# RK3566_Power.net
KiCad netlist of a schematic drawn in Altium Designer
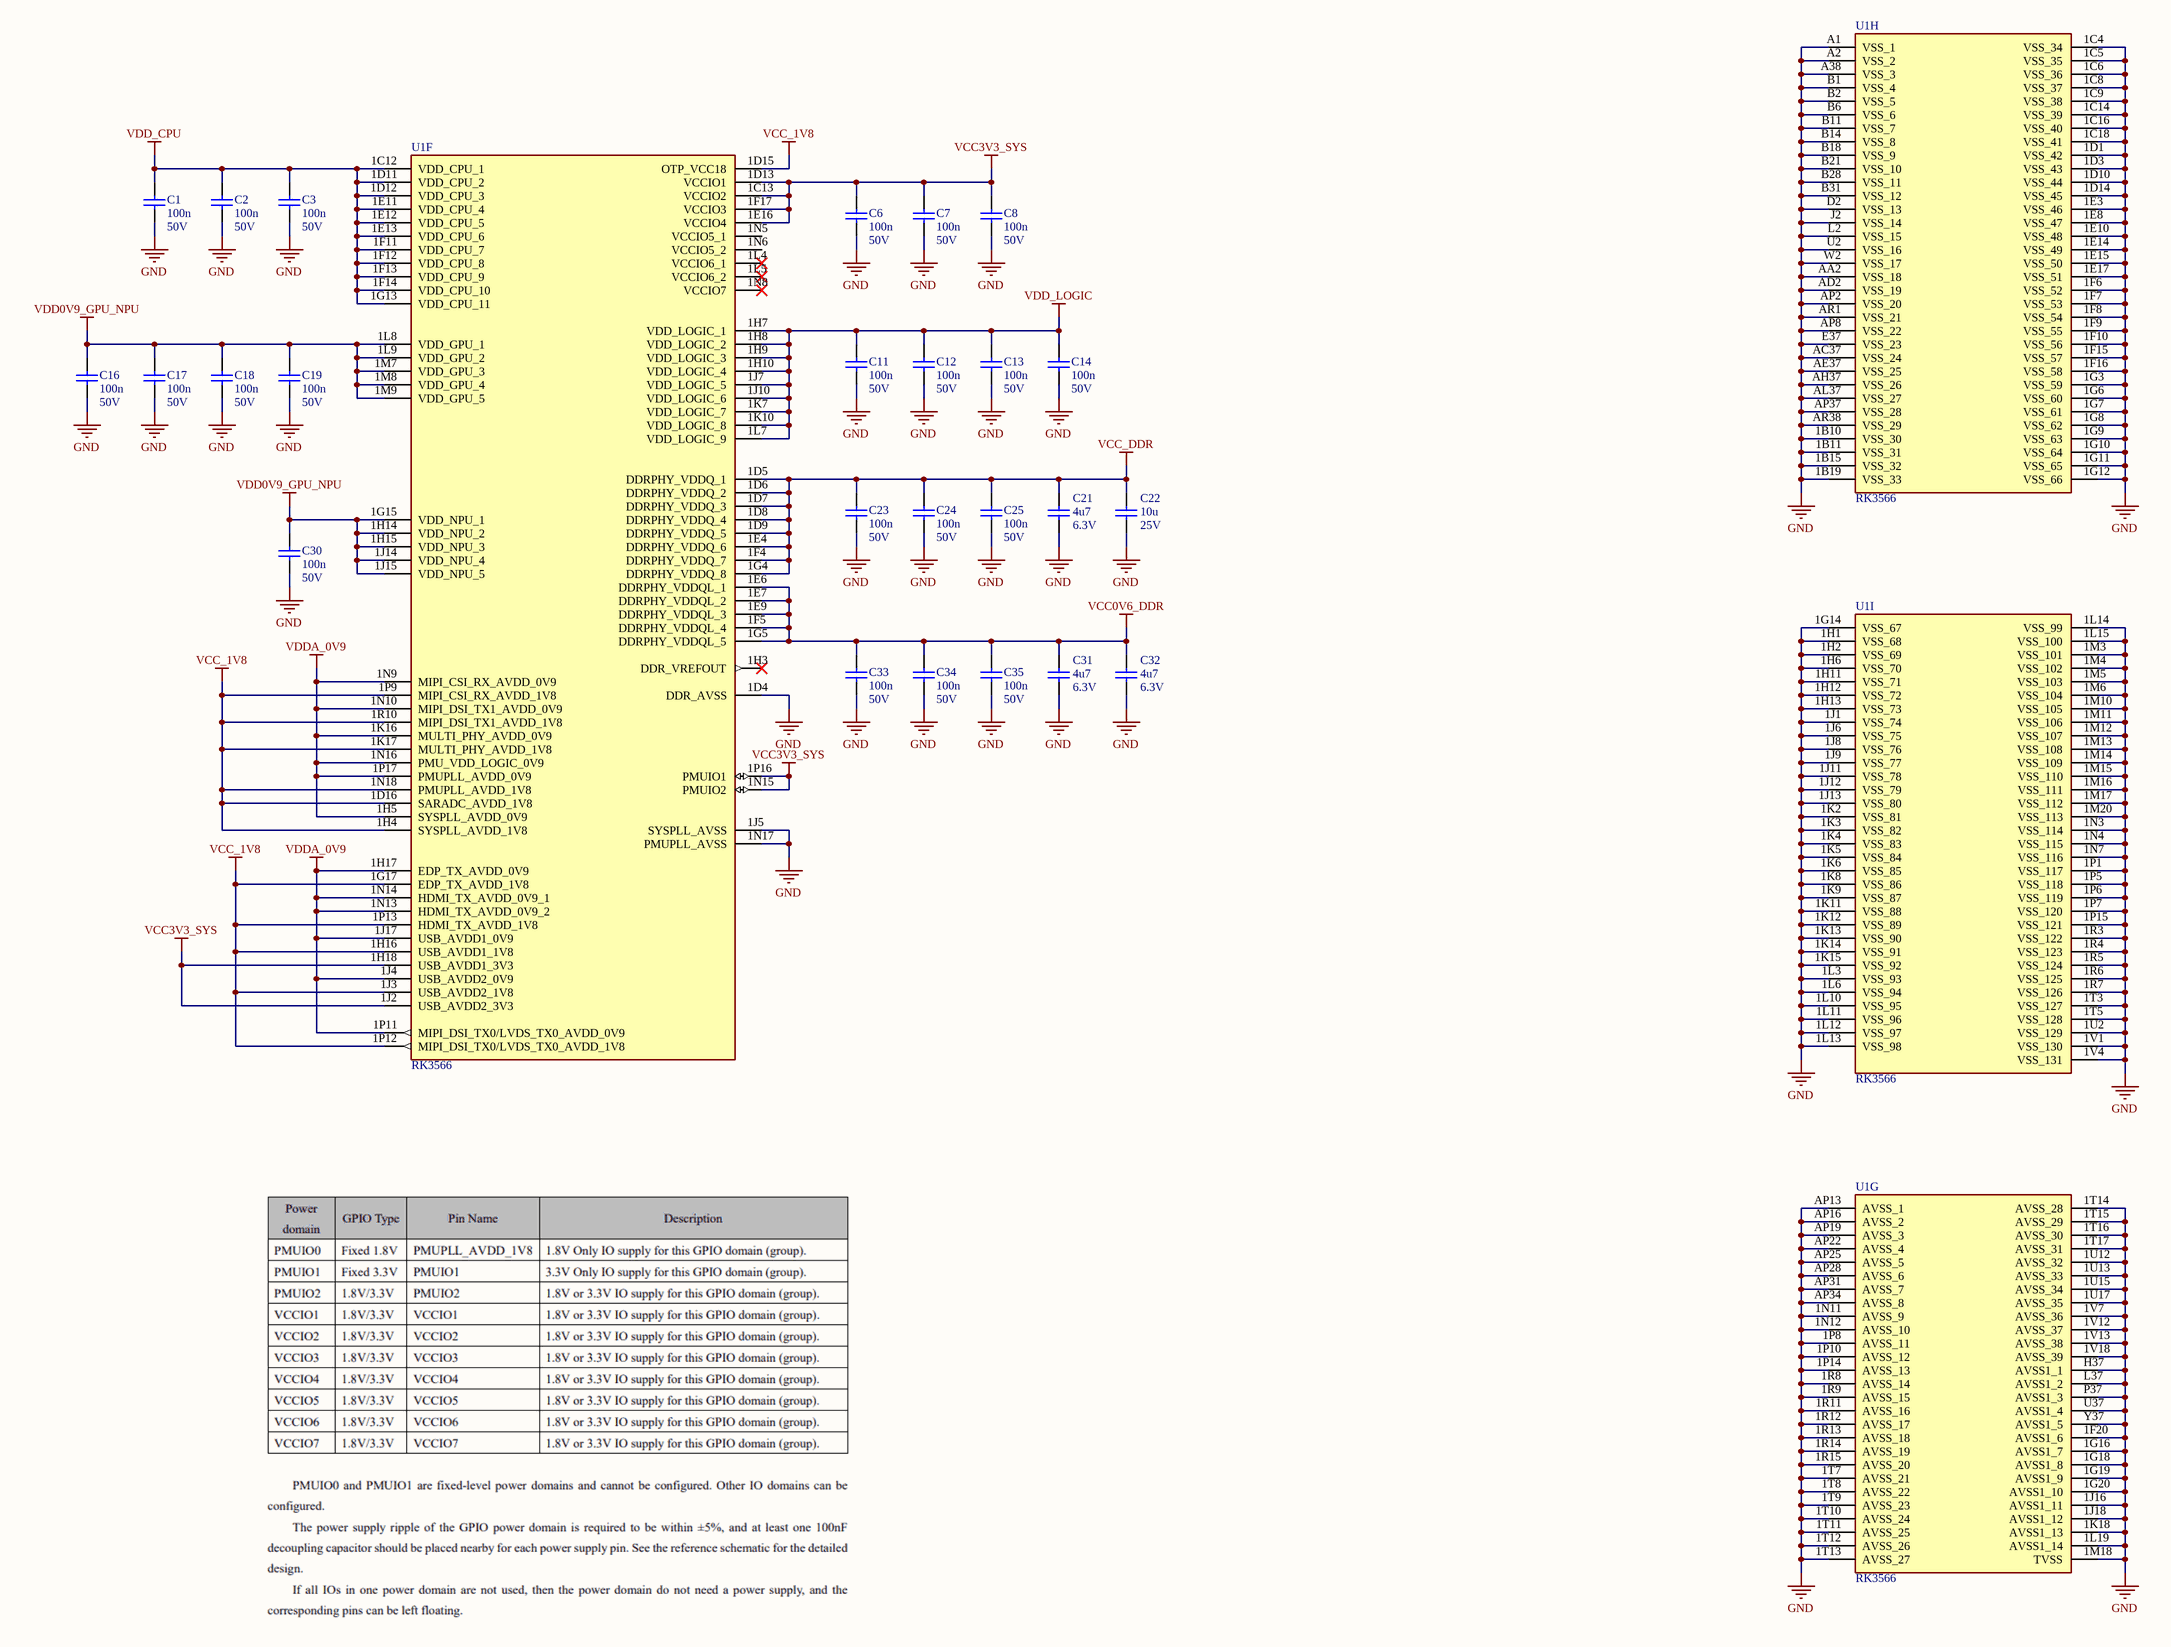
[diagram p0: RK3566_Power.SchDoc]

(export (version "E")
  (design (tool "Eeschema 10.0.6"))
  (components
    (comp (ref "C1")
      (value "100n")
      (footprint "GRM155R71H104KE14D")
      (description "CAP 100N 50V X7R 0402")
      (fields (field (name "VOLTAGE") "50V") (field (name "Comment") "GRM155R71H104KE14D"))
      (libsource (lib "PersonalAltiumLibrary") (part "GRM155R71H104KE14D"))
    )
    (comp (ref "C2")
      (value "100n")
      (footprint "GRM155R71H104KE14D")
      (description "CAP 100N 50V X7R 0402")
      (fields (field (name "VOLTAGE") "50V") (field (name "Comment") "GRM155R71H104KE14D"))
      (libsource (lib "PersonalAltiumLibrary") (part "GRM155R71H104KE14D"))
    )
    (comp (ref "C3")
      (value "100n")
      (footprint "GRM155R71H104KE14D")
      (description "CAP 100N 50V X7R 0402")
      (fields (field (name "VOLTAGE") "50V") (field (name "Comment") "GRM155R71H104KE14D"))
      (libsource (lib "PersonalAltiumLibrary") (part "GRM155R71H104KE14D"))
    )
    (comp (ref "C6")
      (value "100n")
      (footprint "GRM155R71H104KE14D")
      (description "CAP 100N 50V X7R 0402")
      (fields (field (name "VOLTAGE") "50V") (field (name "Comment") "GRM155R71H104KE14D"))
      (libsource (lib "PersonalAltiumLibrary") (part "GRM155R71H104KE14D"))
    )
    (comp (ref "C7")
      (value "100n")
      (footprint "GRM155R71H104KE14D")
      (description "CAP 100N 50V X7R 0402")
      (fields (field (name "VOLTAGE") "50V") (field (name "Comment") "GRM155R71H104KE14D"))
      (libsource (lib "PersonalAltiumLibrary") (part "GRM155R71H104KE14D"))
    )
    (comp (ref "C8")
      (value "100n")
      (footprint "GRM155R71H104KE14D")
      (description "CAP 100N 50V X7R 0402")
      (fields (field (name "VOLTAGE") "50V") (field (name "Comment") "GRM155R71H104KE14D"))
      (libsource (lib "PersonalAltiumLibrary") (part "GRM155R71H104KE14D"))
    )
    (comp (ref "C11")
      (value "100n")
      (footprint "GRM155R71H104KE14D")
      (description "CAP 100N 50V X7R 0402")
      (fields (field (name "VOLTAGE") "50V") (field (name "Comment") "GRM155R71H104KE14D"))
      (libsource (lib "PersonalAltiumLibrary") (part "GRM155R71H104KE14D"))
    )
    (comp (ref "C12")
      (value "100n")
      (footprint "GRM155R71H104KE14D")
      (description "CAP 100N 50V X7R 0402")
      (fields (field (name "VOLTAGE") "50V") (field (name "Comment") "GRM155R71H104KE14D"))
      (libsource (lib "PersonalAltiumLibrary") (part "GRM155R71H104KE14D"))
    )
    (comp (ref "C13")
      (value "100n")
      (footprint "GRM155R71H104KE14D")
      (description "CAP 100N 50V X7R 0402")
      (fields (field (name "VOLTAGE") "50V") (field (name "Comment") "GRM155R71H104KE14D"))
      (libsource (lib "PersonalAltiumLibrary") (part "GRM155R71H104KE14D"))
    )
    (comp (ref "C14")
      (value "100n")
      (footprint "GRM155R71H104KE14D")
      (description "CAP 100N 50V X7R 0402")
      (fields (field (name "VOLTAGE") "50V") (field (name "Comment") "GRM155R71H104KE14D"))
      (libsource (lib "PersonalAltiumLibrary") (part "GRM155R71H104KE14D"))
    )
    (comp (ref "C16")
      (value "100n")
      (footprint "GRM155R71H104KE14D")
      (description "CAP 100N 50V X7R 0402")
      (fields (field (name "VOLTAGE") "50V") (field (name "Comment") "GRM155R71H104KE14D"))
      (libsource (lib "PersonalAltiumLibrary") (part "GRM155R71H104KE14D"))
    )
    (comp (ref "C17")
      (value "100n")
      (footprint "GRM155R71H104KE14D")
      (description "CAP 100N 50V X7R 0402")
      (fields (field (name "VOLTAGE") "50V") (field (name "Comment") "GRM155R71H104KE14D"))
      (libsource (lib "PersonalAltiumLibrary") (part "GRM155R71H104KE14D"))
    )
    (comp (ref "C18")
      (value "100n")
      (footprint "GRM155R71H104KE14D")
      (description "CAP 100N 50V X7R 0402")
      (fields (field (name "VOLTAGE") "50V") (field (name "Comment") "GRM155R71H104KE14D"))
      (libsource (lib "PersonalAltiumLibrary") (part "GRM155R71H104KE14D"))
    )
    (comp (ref "C19")
      (value "100n")
      (footprint "GRM155R71H104KE14D")
      (description "CAP 100N 50V X7R 0402")
      (fields (field (name "VOLTAGE") "50V") (field (name "Comment") "GRM155R71H104KE14D"))
      (libsource (lib "PersonalAltiumLibrary") (part "GRM155R71H104KE14D"))
    )
    (comp (ref "C21")
      (value "4u7")
      (footprint "GRM155R60J475ME47D")
      (description "CAP 4.7U 6.3V X5R 0402")
      (fields (field (name "VOLTAGE") "6.3V") (field (name "Comment") "GRM155R60J475ME47D"))
      (libsource (lib "PersonalAltiumLibrary") (part "GRM155R60J475ME47D"))
    )
    (comp (ref "C22")
      (value "10u")
      (description "CAP 10U 25V X5R 0603")
      (fields (field (name "VOLTAGE") "25V") (field (name "Comment") "GRM188R61E106MA73D"))
      (libsource (lib "PersonalAltiumLibrary") (part "GRM188R61E106MA73D"))
    )
    (comp (ref "C23")
      (value "100n")
      (footprint "GRM155R71H104KE14D")
      (description "CAP 100N 50V X7R 0402")
      (fields (field (name "VOLTAGE") "50V") (field (name "Comment") "GRM155R71H104KE14D"))
      (libsource (lib "PersonalAltiumLibrary") (part "GRM155R71H104KE14D"))
    )
    (comp (ref "C24")
      (value "100n")
      (footprint "GRM155R71H104KE14D")
      (description "CAP 100N 50V X7R 0402")
      (fields (field (name "VOLTAGE") "50V") (field (name "Comment") "GRM155R71H104KE14D"))
      (libsource (lib "PersonalAltiumLibrary") (part "GRM155R71H104KE14D"))
    )
    (comp (ref "C25")
      (value "100n")
      (footprint "GRM155R71H104KE14D")
      (description "CAP 100N 50V X7R 0402")
      (fields (field (name "VOLTAGE") "50V") (field (name "Comment") "GRM155R71H104KE14D"))
      (libsource (lib "PersonalAltiumLibrary") (part "GRM155R71H104KE14D"))
    )
    (comp (ref "C30")
      (value "100n")
      (footprint "GRM155R71H104KE14D")
      (description "CAP 100N 50V X7R 0402")
      (fields (field (name "VOLTAGE") "50V") (field (name "Comment") "GRM155R71H104KE14D"))
      (libsource (lib "PersonalAltiumLibrary") (part "GRM155R71H104KE14D"))
    )
    (comp (ref "C31")
      (value "4u7")
      (footprint "GRM155R60J475ME47D")
      (description "CAP 4.7U 6.3V X5R 0402")
      (fields (field (name "VOLTAGE") "6.3V") (field (name "Comment") "GRM155R60J475ME47D"))
      (libsource (lib "PersonalAltiumLibrary") (part "GRM155R60J475ME47D"))
    )
    (comp (ref "C32")
      (value "4u7")
      (footprint "GRM155R60J475ME47D")
      (description "CAP 4.7U 6.3V X5R 0402")
      (fields (field (name "VOLTAGE") "6.3V") (field (name "Comment") "GRM155R60J475ME47D"))
      (libsource (lib "PersonalAltiumLibrary") (part "GRM155R60J475ME47D"))
    )
    (comp (ref "C33")
      (value "100n")
      (footprint "GRM155R71H104KE14D")
      (description "CAP 100N 50V X7R 0402")
      (fields (field (name "VOLTAGE") "50V") (field (name "Comment") "GRM155R71H104KE14D"))
      (libsource (lib "PersonalAltiumLibrary") (part "GRM155R71H104KE14D"))
    )
    (comp (ref "C34")
      (value "100n")
      (footprint "GRM155R71H104KE14D")
      (description "CAP 100N 50V X7R 0402")
      (fields (field (name "VOLTAGE") "50V") (field (name "Comment") "GRM155R71H104KE14D"))
      (libsource (lib "PersonalAltiumLibrary") (part "GRM155R71H104KE14D"))
    )
    (comp (ref "C35")
      (value "100n")
      (footprint "GRM155R71H104KE14D")
      (description "CAP 100N 50V X7R 0402")
      (fields (field (name "VOLTAGE") "50V") (field (name "Comment") "GRM155R71H104KE14D"))
      (libsource (lib "PersonalAltiumLibrary") (part "GRM155R71H104KE14D"))
    )
    (comp (ref "U1")
      (value "RK3566")
      (footprint "RK3566")
      (description "high-performance and low-power quad-core application processor")
      (fields (field (name "MF") "Fuzhou Rockchip Electronics Co"))
      (libsource (lib "PersonalAltiumLibrary") (part "RK3566"))
    )
  )
  (nets
    (net (code "1") (name "GND") (class "Default")
      (node (ref "C1") (pin "2") (pinfunction "2_2") (pintype "passive"))
      (node (ref "C11") (pin "2") (pinfunction "2_2") (pintype "passive"))
      (node (ref "C12") (pin "2") (pinfunction "2_2") (pintype "passive"))
      (node (ref "C13") (pin "2") (pinfunction "2_2") (pintype "passive"))
      (node (ref "C14") (pin "2") (pinfunction "2_2") (pintype "passive"))
      (node (ref "C16") (pin "2") (pinfunction "2_2") (pintype "passive"))
      (node (ref "C17") (pin "2") (pinfunction "2_2") (pintype "passive"))
      (node (ref "C18") (pin "2") (pinfunction "2_2") (pintype "passive"))
      (node (ref "C19") (pin "2") (pinfunction "2_2") (pintype "passive"))
      (node (ref "C2") (pin "2") (pinfunction "2_2") (pintype "passive"))
      (node (ref "C21") (pin "2") (pinfunction "2_2") (pintype "passive"))
      (node (ref "C22") (pin "2") (pinfunction "2_2") (pintype "passive"))
      (node (ref "C23") (pin "2") (pinfunction "2_2") (pintype "passive"))
      (node (ref "C24") (pin "2") (pinfunction "2_2") (pintype "passive"))
      (node (ref "C25") (pin "2") (pinfunction "2_2") (pintype "passive"))
      (node (ref "C3") (pin "2") (pinfunction "2_2") (pintype "passive"))
      (node (ref "C30") (pin "2") (pinfunction "2_2") (pintype "passive"))
      (node (ref "C31") (pin "2") (pinfunction "2_2") (pintype "passive"))
      (node (ref "C32") (pin "2") (pinfunction "2_2") (pintype "passive"))
      (node (ref "C33") (pin "2") (pinfunction "2_2") (pintype "passive"))
      (node (ref "C34") (pin "2") (pinfunction "2_2") (pintype "passive"))
      (node (ref "C35") (pin "2") (pinfunction "2_2") (pintype "passive"))
      (node (ref "C6") (pin "2") (pinfunction "2_2") (pintype "passive"))
      (node (ref "C7") (pin "2") (pinfunction "2_2") (pintype "passive"))
      (node (ref "C8") (pin "2") (pinfunction "2_2") (pintype "passive"))
      (node (ref "U1") (pin "1B10") (pinfunction "VSS_30_1B10") (pintype "power_in"))
      (node (ref "U1") (pin "1B11") (pinfunction "VSS_31_1B11") (pintype "power_in"))
      (node (ref "U1") (pin "1B15") (pinfunction "VSS_32_1B15") (pintype "power_in"))
      (node (ref "U1") (pin "1B19") (pinfunction "VSS_33_1B19") (pintype "power_in"))
      (node (ref "U1") (pin "1C14") (pinfunction "VSS_39_1C14") (pintype "power_in"))
      (node (ref "U1") (pin "1C16") (pinfunction "VSS_40_1C16") (pintype "power_in"))
      (node (ref "U1") (pin "1C18") (pinfunction "VSS_41_1C18") (pintype "power_in"))
      (node (ref "U1") (pin "1C4") (pinfunction "VSS_34_1C4") (pintype "power_in"))
      (node (ref "U1") (pin "1C5") (pinfunction "VSS_35_1C5") (pintype "power_in"))
      (node (ref "U1") (pin "1C6") (pinfunction "VSS_36_1C6") (pintype "power_in"))
      (node (ref "U1") (pin "1C8") (pinfunction "VSS_37_1C8") (pintype "power_in"))
      (node (ref "U1") (pin "1C9") (pinfunction "VSS_38_1C9") (pintype "power_in"))
      (node (ref "U1") (pin "1D1") (pinfunction "VSS_42_1D1") (pintype "power_in"))
      (node (ref "U1") (pin "1D10") (pinfunction "VSS_44_1D10") (pintype "power_in"))
      (node (ref "U1") (pin "1D14") (pinfunction "VSS_45_1D14") (pintype "power_in"))
      (node (ref "U1") (pin "1D3") (pinfunction "VSS_43_1D3") (pintype "power_in"))
      (node (ref "U1") (pin "1D4") (pinfunction "DDR_AVSS_1D4") (pintype "power_in"))
      (node (ref "U1") (pin "1E10") (pinfunction "VSS_48_1E10") (pintype "power_in"))
      (node (ref "U1") (pin "1E14") (pinfunction "VSS_49_1E14") (pintype "power_in"))
      (node (ref "U1") (pin "1E15") (pinfunction "VSS_50_1E15") (pintype "power_in"))
      (node (ref "U1") (pin "1E17") (pinfunction "VSS_51_1E17") (pintype "power_in"))
      (node (ref "U1") (pin "1E3") (pinfunction "VSS_46_1E3") (pintype "power_in"))
      (node (ref "U1") (pin "1E8") (pinfunction "VSS_47_1E8") (pintype "power_in"))
      (node (ref "U1") (pin "1F10") (pinfunction "VSS_56_1F10") (pintype "power_in"))
      (node (ref "U1") (pin "1F15") (pinfunction "VSS_57_1F15") (pintype "power_in"))
      (node (ref "U1") (pin "1F16") (pinfunction "VSS_58_1F16") (pintype "power_in"))
      (node (ref "U1") (pin "1F20") (pinfunction "AVSS1_6_1F20") (pintype "power_in"))
      (node (ref "U1") (pin "1F6") (pinfunction "VSS_52_1F6") (pintype "power_in"))
      (node (ref "U1") (pin "1F7") (pinfunction "VSS_53_1F7") (pintype "power_in"))
      (node (ref "U1") (pin "1F8") (pinfunction "VSS_54_1F8") (pintype "power_in"))
      (node (ref "U1") (pin "1F9") (pinfunction "VSS_55_1F9") (pintype "power_in"))
      (node (ref "U1") (pin "1G10") (pinfunction "VSS_64_1G10") (pintype "power_in"))
      (node (ref "U1") (pin "1G11") (pinfunction "VSS_65_1G11") (pintype "power_in"))
      (node (ref "U1") (pin "1G12") (pinfunction "VSS_66_1G12") (pintype "power_in"))
      (node (ref "U1") (pin "1G14") (pinfunction "VSS_67_1G14") (pintype "power_in"))
      (node (ref "U1") (pin "1G16") (pinfunction "AVSS1_7_1G16") (pintype "power_in"))
      (node (ref "U1") (pin "1G18") (pinfunction "AVSS1_8_1G18") (pintype "power_in"))
      (node (ref "U1") (pin "1G19") (pinfunction "AVSS1_9_1G19") (pintype "power_in"))
      (node (ref "U1") (pin "1G20") (pinfunction "AVSS1_10_1G20") (pintype "power_in"))
      (node (ref "U1") (pin "1G3") (pinfunction "VSS_59_1G3") (pintype "power_in"))
      (node (ref "U1") (pin "1G6") (pinfunction "VSS_60_1G6") (pintype "power_in"))
      (node (ref "U1") (pin "1G7") (pinfunction "VSS_61_1G7") (pintype "power_in"))
      (node (ref "U1") (pin "1G8") (pinfunction "VSS_62_1G8") (pintype "power_in"))
      (node (ref "U1") (pin "1G9") (pinfunction "VSS_63_1G9") (pintype "power_in"))
      (node (ref "U1") (pin "1H1") (pinfunction "VSS_68_1H1") (pintype "power_in"))
      (node (ref "U1") (pin "1H11") (pinfunction "VSS_71_1H11") (pintype "power_in"))
      (node (ref "U1") (pin "1H12") (pinfunction "VSS_72_1H12") (pintype "power_in"))
      (node (ref "U1") (pin "1H13") (pinfunction "VSS_73_1H13") (pintype "power_in"))
      (node (ref "U1") (pin "1H2") (pinfunction "VSS_69_1H2") (pintype "power_in"))
      (node (ref "U1") (pin "1H6") (pinfunction "VSS_70_1H6") (pintype "power_in"))
      (node (ref "U1") (pin "1J1") (pinfunction "VSS_74_1J1") (pintype "power_in"))
      (node (ref "U1") (pin "1J11") (pinfunction "VSS_78_1J11") (pintype "power_in"))
      (node (ref "U1") (pin "1J12") (pinfunction "VSS_79_1J12") (pintype "power_in"))
      (node (ref "U1") (pin "1J13") (pinfunction "VSS_80_1J13") (pintype "power_in"))
      (node (ref "U1") (pin "1J16") (pinfunction "AVSS1_11_1J16") (pintype "power_in"))
      (node (ref "U1") (pin "1J18") (pinfunction "AVSS1_12_1J18") (pintype "power_in"))
      (node (ref "U1") (pin "1J5") (pinfunction "SYSPLL_AVSS_1J5") (pintype "power_in"))
      (node (ref "U1") (pin "1J6") (pinfunction "VSS_75_1J6") (pintype "power_in"))
      (node (ref "U1") (pin "1J8") (pinfunction "VSS_76_1J8") (pintype "power_in"))
      (node (ref "U1") (pin "1J9") (pinfunction "VSS_77_1J9") (pintype "power_in"))
      (node (ref "U1") (pin "1K11") (pinfunction "VSS_88_1K11") (pintype "power_in"))
      (node (ref "U1") (pin "1K12") (pinfunction "VSS_89_1K12") (pintype "power_in"))
      (node (ref "U1") (pin "1K13") (pinfunction "VSS_90_1K13") (pintype "power_in"))
      (node (ref "U1") (pin "1K14") (pinfunction "VSS_91_1K14") (pintype "power_in"))
      (node (ref "U1") (pin "1K15") (pinfunction "VSS_92_1K15") (pintype "power_in"))
      (node (ref "U1") (pin "1K18") (pinfunction "AVSS1_13_1K18") (pintype "power_in"))
      (node (ref "U1") (pin "1K2") (pinfunction "VSS_81_1K2") (pintype "power_in"))
      (node (ref "U1") (pin "1K3") (pinfunction "VSS_82_1K3") (pintype "power_in"))
      (node (ref "U1") (pin "1K4") (pinfunction "VSS_83_1K4") (pintype "power_in"))
      (node (ref "U1") (pin "1K5") (pinfunction "VSS_84_1K5") (pintype "power_in"))
      (node (ref "U1") (pin "1K6") (pinfunction "VSS_85_1K6") (pintype "power_in"))
      (node (ref "U1") (pin "1K8") (pinfunction "VSS_86_1K8") (pintype "power_in"))
      (node (ref "U1") (pin "1K9") (pinfunction "VSS_87_1K9") (pintype "power_in"))
      (node (ref "U1") (pin "1L10") (pinfunction "VSS_95_1L10") (pintype "power_in"))
      (node (ref "U1") (pin "1L11") (pinfunction "VSS_96_1L11") (pintype "power_in"))
      (node (ref "U1") (pin "1L12") (pinfunction "VSS_97_1L12") (pintype "power_in"))
      (node (ref "U1") (pin "1L13") (pinfunction "VSS_98_1L13") (pintype "power_in"))
      (node (ref "U1") (pin "1L14") (pinfunction "VSS_99_1L14") (pintype "power_in"))
      (node (ref "U1") (pin "1L15") (pinfunction "VSS_100_1L15") (pintype "power_in"))
      (node (ref "U1") (pin "1L19") (pinfunction "AVSS1_14_1L19") (pintype "power_in"))
      (node (ref "U1") (pin "1L3") (pinfunction "VSS_93_1L3") (pintype "power_in"))
      (node (ref "U1") (pin "1L6") (pinfunction "VSS_94_1L6") (pintype "power_in"))
      (node (ref "U1") (pin "1M10") (pinfunction "VSS_105_1M10") (pintype "power_in"))
      (node (ref "U1") (pin "1M11") (pinfunction "VSS_106_1M11") (pintype "power_in"))
      (node (ref "U1") (pin "1M12") (pinfunction "VSS_107_1M12") (pintype "power_in"))
      (node (ref "U1") (pin "1M13") (pinfunction "VSS_108_1M13") (pintype "power_in"))
      (node (ref "U1") (pin "1M14") (pinfunction "VSS_109_1M14") (pintype "power_in"))
      (node (ref "U1") (pin "1M15") (pinfunction "VSS_110_1M15") (pintype "power_in"))
      (node (ref "U1") (pin "1M16") (pinfunction "VSS_111_1M16") (pintype "power_in"))
      (node (ref "U1") (pin "1M17") (pinfunction "VSS_112_1M17") (pintype "power_in"))
      (node (ref "U1") (pin "1M18") (pinfunction "TVSS_1M18") (pintype "power_in"))
      (node (ref "U1") (pin "1M20") (pinfunction "VSS_113_1M20") (pintype "power_in"))
      (node (ref "U1") (pin "1M3") (pinfunction "VSS_101_1M3") (pintype "power_in"))
      (node (ref "U1") (pin "1M4") (pinfunction "VSS_102_1M4") (pintype "power_in"))
      (node (ref "U1") (pin "1M5") (pinfunction "VSS_103_1M5") (pintype "power_in"))
      (node (ref "U1") (pin "1M6") (pinfunction "VSS_104_1M6") (pintype "power_in"))
      (node (ref "U1") (pin "1N11") (pinfunction "AVSS_9_1N11") (pintype "power_in"))
      (node (ref "U1") (pin "1N12") (pinfunction "AVSS_10_1N12") (pintype "power_in"))
      (node (ref "U1") (pin "1N17") (pinfunction "PMUPLL_AVSS_1N17") (pintype "power_in"))
      (node (ref "U1") (pin "1N3") (pinfunction "VSS_114_1N3") (pintype "power_in"))
      (node (ref "U1") (pin "1N4") (pinfunction "VSS_115_1N4") (pintype "power_in"))
      (node (ref "U1") (pin "1N7") (pinfunction "VSS_116_1N7") (pintype "power_in"))
      (node (ref "U1") (pin "1P1") (pinfunction "VSS_117_1P1") (pintype "power_in"))
      (node (ref "U1") (pin "1P10") (pinfunction "AVSS_12_1P10") (pintype "power_in"))
      (node (ref "U1") (pin "1P14") (pinfunction "AVSS_13_1P14") (pintype "power_in"))
      (node (ref "U1") (pin "1P15") (pinfunction "VSS_121_1P15") (pintype "power_in"))
      (node (ref "U1") (pin "1P5") (pinfunction "VSS_118_1P5") (pintype "power_in"))
      (node (ref "U1") (pin "1P6") (pinfunction "VSS_119_1P6") (pintype "power_in"))
      (node (ref "U1") (pin "1P7") (pinfunction "VSS_120_1P7") (pintype "power_in"))
      (node (ref "U1") (pin "1P8") (pinfunction "AVSS_11_1P8") (pintype "power_in"))
      (node (ref "U1") (pin "1R11") (pinfunction "AVSS_16_1R11") (pintype "power_in"))
      (node (ref "U1") (pin "1R12") (pinfunction "AVSS_17_1R12") (pintype "power_in"))
      (node (ref "U1") (pin "1R13") (pinfunction "AVSS_18_1R13") (pintype "power_in"))
      (node (ref "U1") (pin "1R14") (pinfunction "AVSS_19_1R14") (pintype "power_in"))
      (node (ref "U1") (pin "1R15") (pinfunction "AVSS_20_1R15") (pintype "power_in"))
      (node (ref "U1") (pin "1R3") (pinfunction "VSS_122_1R3") (pintype "power_in"))
      (node (ref "U1") (pin "1R4") (pinfunction "VSS_123_1R4") (pintype "power_in"))
      (node (ref "U1") (pin "1R5") (pinfunction "VSS_124_1R5") (pintype "power_in"))
      (node (ref "U1") (pin "1R6") (pinfunction "VSS_125_1R6") (pintype "power_in"))
      (node (ref "U1") (pin "1R7") (pinfunction "VSS_126_1R7") (pintype "power_in"))
      (node (ref "U1") (pin "1R8") (pinfunction "AVSS_14_1R8") (pintype "power_in"))
      (node (ref "U1") (pin "1R9") (pinfunction "AVSS_15_1R9") (pintype "power_in"))
      (node (ref "U1") (pin "1T10") (pinfunction "AVSS_24_1T10") (pintype "power_in"))
      (node (ref "U1") (pin "1T11") (pinfunction "AVSS_25_1T11") (pintype "power_in"))
      (node (ref "U1") (pin "1T12") (pinfunction "AVSS_26_1T12") (pintype "power_in"))
      (node (ref "U1") (pin "1T13") (pinfunction "AVSS_27_1T13") (pintype "power_in"))
      (node (ref "U1") (pin "1T14") (pinfunction "AVSS_28_1T14") (pintype "power_in"))
      (node (ref "U1") (pin "1T15") (pinfunction "AVSS_29_1T15") (pintype "power_in"))
      (node (ref "U1") (pin "1T16") (pinfunction "AVSS_30_1T16") (pintype "power_in"))
      (node (ref "U1") (pin "1T17") (pinfunction "AVSS_31_1T17") (pintype "power_in"))
      (node (ref "U1") (pin "1T3") (pinfunction "VSS_127_1T3") (pintype "power_in"))
      (node (ref "U1") (pin "1T5") (pinfunction "VSS_128_1T5") (pintype "power_in"))
      (node (ref "U1") (pin "1T7") (pinfunction "AVSS_21_1T7") (pintype "power_in"))
      (node (ref "U1") (pin "1T8") (pinfunction "AVSS_22_1T8") (pintype "power_in"))
      (node (ref "U1") (pin "1T9") (pinfunction "AVSS_23_1T9") (pintype "power_in"))
      (node (ref "U1") (pin "1U12") (pinfunction "AVSS_32_1U12") (pintype "power_in"))
      (node (ref "U1") (pin "1U13") (pinfunction "AVSS_33_1U13") (pintype "power_in"))
      (node (ref "U1") (pin "1U15") (pinfunction "AVSS_34_1U15") (pintype "power_in"))
      (node (ref "U1") (pin "1U17") (pinfunction "AVSS_35_1U17") (pintype "power_in"))
      (node (ref "U1") (pin "1U2") (pinfunction "VSS_129_1U2") (pintype "power_in"))
      (node (ref "U1") (pin "1V1") (pinfunction "VSS_130_1V1") (pintype "power_in"))
      (node (ref "U1") (pin "1V12") (pinfunction "AVSS_37_1V12") (pintype "power_in"))
      (node (ref "U1") (pin "1V13") (pinfunction "AVSS_38_1V13") (pintype "power_in"))
      (node (ref "U1") (pin "1V18") (pinfunction "AVSS_39_1V18") (pintype "power_in"))
      (node (ref "U1") (pin "1V4") (pinfunction "VSS_131_1V4") (pintype "power_in"))
      (node (ref "U1") (pin "1V7") (pinfunction "AVSS_36_1V7") (pintype "power_in"))
      (node (ref "U1") (pin "A1") (pinfunction "VSS_1_A1") (pintype "power_in"))
      (node (ref "U1") (pin "A2") (pinfunction "VSS_2_A2") (pintype "power_in"))
      (node (ref "U1") (pin "A38") (pinfunction "VSS_3_A38") (pintype "power_in"))
      (node (ref "U1") (pin "AA2") (pinfunction "VSS_18_AA2") (pintype "power_in"))
      (node (ref "U1") (pin "AC37") (pinfunction "VSS_24_AC37") (pintype "power_in"))
      (node (ref "U1") (pin "AD2") (pinfunction "VSS_19_AD2") (pintype "power_in"))
      (node (ref "U1") (pin "AE37") (pinfunction "VSS_25_AE37") (pintype "power_in"))
      (node (ref "U1") (pin "AH37") (pinfunction "VSS_26_AH37") (pintype "power_in"))
      (node (ref "U1") (pin "AL37") (pinfunction "VSS_27_AL37") (pintype "power_in"))
      (node (ref "U1") (pin "AP13") (pinfunction "AVSS_1_AP13") (pintype "power_in"))
      (node (ref "U1") (pin "AP16") (pinfunction "AVSS_2_AP16") (pintype "power_in"))
      (node (ref "U1") (pin "AP19") (pinfunction "AVSS_3_AP19") (pintype "power_in"))
      (node (ref "U1") (pin "AP2") (pinfunction "VSS_20_AP2") (pintype "power_in"))
      (node (ref "U1") (pin "AP22") (pinfunction "AVSS_4_AP22") (pintype "power_in"))
      (node (ref "U1") (pin "AP25") (pinfunction "AVSS_5_AP25") (pintype "power_in"))
      (node (ref "U1") (pin "AP28") (pinfunction "AVSS_6_AP28") (pintype "power_in"))
      (node (ref "U1") (pin "AP31") (pinfunction "AVSS_7_AP31") (pintype "power_in"))
      (node (ref "U1") (pin "AP34") (pinfunction "AVSS_8_AP34") (pintype "power_in"))
      (node (ref "U1") (pin "AP37") (pinfunction "VSS_28_AP37") (pintype "power_in"))
      (node (ref "U1") (pin "AP8") (pinfunction "VSS_22_AP8") (pintype "power_in"))
      (node (ref "U1") (pin "AR1") (pinfunction "VSS_21_AR1") (pintype "power_in"))
      (node (ref "U1") (pin "AR38") (pinfunction "VSS_29_AR38") (pintype "power_in"))
      (node (ref "U1") (pin "B1") (pinfunction "VSS_4_B1") (pintype "power_in"))
      (node (ref "U1") (pin "B11") (pinfunction "VSS_7_B11") (pintype "power_in"))
      (node (ref "U1") (pin "B14") (pinfunction "VSS_8_B14") (pintype "power_in"))
      (node (ref "U1") (pin "B18") (pinfunction "VSS_9_B18") (pintype "power_in"))
      (node (ref "U1") (pin "B2") (pinfunction "VSS_5_B2") (pintype "power_in"))
      (node (ref "U1") (pin "B21") (pinfunction "VSS_10_B21") (pintype "power_in"))
      (node (ref "U1") (pin "B28") (pinfunction "VSS_11_B28") (pintype "power_in"))
      (node (ref "U1") (pin "B31") (pinfunction "VSS_12_B31") (pintype "power_in"))
      (node (ref "U1") (pin "B6") (pinfunction "VSS_6_B6") (pintype "power_in"))
      (node (ref "U1") (pin "D2") (pinfunction "VSS_13_D2") (pintype "power_in"))
      (node (ref "U1") (pin "E37") (pinfunction "VSS_23_E37") (pintype "power_in"))
      (node (ref "U1") (pin "H37") (pinfunction "AVSS1_1_H37") (pintype "power_in"))
      (node (ref "U1") (pin "J2") (pinfunction "VSS_14_J2") (pintype "power_in"))
      (node (ref "U1") (pin "L2") (pinfunction "VSS_15_L2") (pintype "power_in"))
      (node (ref "U1") (pin "L37") (pinfunction "AVSS1_2_L37") (pintype "power_in"))
      (node (ref "U1") (pin "P37") (pinfunction "AVSS1_3_P37") (pintype "power_in"))
      (node (ref "U1") (pin "U2") (pinfunction "VSS_16_U2") (pintype "power_in"))
      (node (ref "U1") (pin "U37") (pinfunction "AVSS1_4_U37") (pintype "power_in"))
      (node (ref "U1") (pin "W2") (pinfunction "VSS_17_W2") (pintype "power_in"))
      (node (ref "U1") (pin "Y37") (pinfunction "AVSS1_5_Y37") (pintype "power_in"))
    )
    (net (code "2") (name "VCC0V6_DDR") (class "Default")
      (node (ref "C31") (pin "1") (pinfunction "1_1") (pintype "passive"))
      (node (ref "C32") (pin "1") (pinfunction "1_1") (pintype "passive"))
      (node (ref "C33") (pin "1") (pinfunction "1_1") (pintype "passive"))
      (node (ref "C34") (pin "1") (pinfunction "1_1") (pintype "passive"))
      (node (ref "C35") (pin "1") (pinfunction "1_1") (pintype "passive"))
      (node (ref "U1") (pin "1E6") (pinfunction "DDRPHY_VDDQL_1_1E6") (pintype "power_in"))
      (node (ref "U1") (pin "1E7") (pinfunction "DDRPHY_VDDQL_2_1E7") (pintype "power_in"))
      (node (ref "U1") (pin "1E9") (pinfunction "DDRPHY_VDDQL_3_1E9") (pintype "power_in"))
      (node (ref "U1") (pin "1F5") (pinfunction "DDRPHY_VDDQL_4_1F5") (pintype "power_in"))
      (node (ref "U1") (pin "1G5") (pinfunction "DDRPHY_VDDQL_5_1G5") (pintype "power_in"))
    )
    (net (code "3") (name "VCC3V3_SYS") (class "Default")
      (node (ref "C6") (pin "1") (pinfunction "1_1") (pintype "passive"))
      (node (ref "C7") (pin "1") (pinfunction "1_1") (pintype "passive"))
      (node (ref "C8") (pin "1") (pinfunction "1_1") (pintype "passive"))
      (node (ref "U1") (pin "1C13") (pinfunction "VCCIO2_1C13") (pintype "power_in"))
      (node (ref "U1") (pin "1D13") (pinfunction "VCCIO1_1D13") (pintype "power_in"))
      (node (ref "U1") (pin "1E16") (pinfunction "VCCIO4_1E16") (pintype "power_in"))
      (node (ref "U1") (pin "1F17") (pinfunction "VCCIO3_1F17") (pintype "power_in"))
      (node (ref "U1") (pin "1H18") (pinfunction "USB_AVDD1_3V3_1H18") (pintype "power_in"))
      (node (ref "U1") (pin "1J2") (pinfunction "USB_AVDD2_3V3_1J2") (pintype "power_in"))
      (node (ref "U1") (pin "1N15") (pinfunction "PMUIO2_1N15") (pintype "bidirectional"))
      (node (ref "U1") (pin "1P16") (pinfunction "PMUIO1_1P16") (pintype "bidirectional"))
    )
    (net (code "4") (name "VCC_1V8") (class "Default")
      (node (ref "U1") (pin "1D15") (pinfunction "OTP_VCC18_1D15") (pintype "power_in"))
      (node (ref "U1") (pin "1D16") (pinfunction "SARADC_AVDD_1V8_1D16") (pintype "power_in"))
      (node (ref "U1") (pin "1G17") (pinfunction "EDP_TX_AVDD_1V8_1G17") (pintype "power_in"))
      (node (ref "U1") (pin "1H16") (pinfunction "USB_AVDD1_1V8_1H16") (pintype "power_in"))
      (node (ref "U1") (pin "1H4") (pinfunction "SYSPLL_AVDD_1V8_1H4") (pintype "power_in"))
      (node (ref "U1") (pin "1J3") (pinfunction "USB_AVDD2_1V8_1J3") (pintype "power_in"))
      (node (ref "U1") (pin "1K17") (pinfunction "MULTI_PHY_AVDD_1V8_1K17") (pintype "power_in"))
      (node (ref "U1") (pin "1N18") (pinfunction "PMUPLL_AVDD_1V8_1N18") (pintype "power_in"))
      (node (ref "U1") (pin "1P12") (pinfunction "MIPI_DSI_TX0/LVDS_TX0_AVDD_1V8_1P12") (pintype "output"))
      (node (ref "U1") (pin "1P13") (pinfunction "HDMI_TX_AVDD_1V8_1P13") (pintype "power_in"))
      (node (ref "U1") (pin "1P9") (pinfunction "MIPI_CSI_RX_AVDD_1V8_1P9") (pintype "power_in"))
      (node (ref "U1") (pin "1R10") (pinfunction "MIPI_DSI_TX1_AVDD_1V8_1R10") (pintype "power_in"))
    )
    (net (code "5") (name "VCC_DDR") (class "Default")
      (node (ref "C21") (pin "1") (pinfunction "1_1") (pintype "passive"))
      (node (ref "C22") (pin "1") (pinfunction "1_1") (pintype "passive"))
      (node (ref "C23") (pin "1") (pinfunction "1_1") (pintype "passive"))
      (node (ref "C24") (pin "1") (pinfunction "1_1") (pintype "passive"))
      (node (ref "C25") (pin "1") (pinfunction "1_1") (pintype "passive"))
      (node (ref "U1") (pin "1D5") (pinfunction "DDRPHY_VDDQ_1_1D5") (pintype "power_in"))
      (node (ref "U1") (pin "1D6") (pinfunction "DDRPHY_VDDQ_2_1D6") (pintype "power_in"))
      (node (ref "U1") (pin "1D7") (pinfunction "DDRPHY_VDDQ_3_1D7") (pintype "power_in"))
      (node (ref "U1") (pin "1D8") (pinfunction "DDRPHY_VDDQ_4_1D8") (pintype "power_in"))
      (node (ref "U1") (pin "1D9") (pinfunction "DDRPHY_VDDQ_5_1D9") (pintype "power_in"))
      (node (ref "U1") (pin "1E4") (pinfunction "DDRPHY_VDDQ_6_1E4") (pintype "power_in"))
      (node (ref "U1") (pin "1F4") (pinfunction "DDRPHY_VDDQ_7_1F4") (pintype "power_in"))
      (node (ref "U1") (pin "1G4") (pinfunction "DDRPHY_VDDQ_8_1G4") (pintype "power_in"))
    )
    (net (code "6") (name "VDD0V9_GPU_NPU") (class "Default")
      (node (ref "C16") (pin "1") (pinfunction "1_1") (pintype "passive"))
      (node (ref "C17") (pin "1") (pinfunction "1_1") (pintype "passive"))
      (node (ref "C18") (pin "1") (pinfunction "1_1") (pintype "passive"))
      (node (ref "C19") (pin "1") (pinfunction "1_1") (pintype "passive"))
      (node (ref "C30") (pin "1") (pinfunction "1_1") (pintype "passive"))
      (node (ref "U1") (pin "1G15") (pinfunction "VDD_NPU_1_1G15") (pintype "power_in"))
      (node (ref "U1") (pin "1H14") (pinfunction "VDD_NPU_2_1H14") (pintype "power_in"))
      (node (ref "U1") (pin "1H15") (pinfunction "VDD_NPU_3_1H15") (pintype "power_in"))
      (node (ref "U1") (pin "1J14") (pinfunction "VDD_NPU_4_1J14") (pintype "power_in"))
      (node (ref "U1") (pin "1J15") (pinfunction "VDD_NPU_5_1J15") (pintype "power_in"))
      (node (ref "U1") (pin "1L8") (pinfunction "VDD_GPU_1_1L8") (pintype "power_in"))
      (node (ref "U1") (pin "1L9") (pinfunction "VDD_GPU_2_1L9") (pintype "power_in"))
      (node (ref "U1") (pin "1M7") (pinfunction "VDD_GPU_3_1M7") (pintype "power_in"))
      (node (ref "U1") (pin "1M8") (pinfunction "VDD_GPU_4_1M8") (pintype "power_in"))
      (node (ref "U1") (pin "1M9") (pinfunction "VDD_GPU_5_1M9") (pintype "power_in"))
    )
    (net (code "7") (name "VDDA_0V9") (class "Default")
      (node (ref "U1") (pin "1H17") (pinfunction "EDP_TX_AVDD_0V9_1H17") (pintype "power_in"))
      (node (ref "U1") (pin "1H5") (pinfunction "SYSPLL_AVDD_0V9_1H5") (pintype "power_in"))
      (node (ref "U1") (pin "1J17") (pinfunction "USB_AVDD1_0V9_1J17") (pintype "power_in"))
      (node (ref "U1") (pin "1J4") (pinfunction "USB_AVDD2_0V9_1J4") (pintype "power_in"))
      (node (ref "U1") (pin "1K16") (pinfunction "MULTI_PHY_AVDD_0V9_1K16") (pintype "power_in"))
      (node (ref "U1") (pin "1N10") (pinfunction "MIPI_DSI_TX1_AVDD_0V9_1N10") (pintype "power_in"))
      (node (ref "U1") (pin "1N13") (pinfunction "HDMI_TX_AVDD_0V9_2_1N13") (pintype "power_in"))
      (node (ref "U1") (pin "1N14") (pinfunction "HDMI_TX_AVDD_0V9_1_1N14") (pintype "power_in"))
      (node (ref "U1") (pin "1N16") (pinfunction "PMU_VDD_LOGIC_0V9_1N16") (pintype "power_in"))
      (node (ref "U1") (pin "1N9") (pinfunction "MIPI_CSI_RX_AVDD_0V9_1N9") (pintype "power_in"))
      (node (ref "U1") (pin "1P11") (pinfunction "MIPI_DSI_TX0/LVDS_TX0_AVDD_0V9_1P11") (pintype "output"))
      (node (ref "U1") (pin "1P17") (pinfunction "PMUPLL_AVDD_0V9_1P17") (pintype "power_in"))
    )
    (net (code "8") (name "VDD_CPU") (class "Default")
      (node (ref "C1") (pin "1") (pinfunction "1_1") (pintype "passive"))
      (node (ref "C2") (pin "1") (pinfunction "1_1") (pintype "passive"))
      (node (ref "C3") (pin "1") (pinfunction "1_1") (pintype "passive"))
      (node (ref "U1") (pin "1C12") (pinfunction "VDD_CPU_1_1C12") (pintype "power_in"))
      (node (ref "U1") (pin "1D11") (pinfunction "VDD_CPU_2_1D11") (pintype "power_in"))
      (node (ref "U1") (pin "1D12") (pinfunction "VDD_CPU_3_1D12") (pintype "power_in"))
      (node (ref "U1") (pin "1E11") (pinfunction "VDD_CPU_4_1E11") (pintype "power_in"))
      (node (ref "U1") (pin "1E12") (pinfunction "VDD_CPU_5_1E12") (pintype "power_in"))
      (node (ref "U1") (pin "1E13") (pinfunction "VDD_CPU_6_1E13") (pintype "power_in"))
      (node (ref "U1") (pin "1F11") (pinfunction "VDD_CPU_7_1F11") (pintype "power_in"))
      (node (ref "U1") (pin "1F12") (pinfunction "VDD_CPU_8_1F12") (pintype "power_in"))
      (node (ref "U1") (pin "1F13") (pinfunction "VDD_CPU_9_1F13") (pintype "power_in"))
      (node (ref "U1") (pin "1F14") (pinfunction "VDD_CPU_10_1F14") (pintype "power_in"))
      (node (ref "U1") (pin "1G13") (pinfunction "VDD_CPU_11_1G13") (pintype "power_in"))
    )
    (net (code "9") (name "VDD_LOGIC") (class "Default")
      (node (ref "C11") (pin "1") (pinfunction "1_1") (pintype "passive"))
      (node (ref "C12") (pin "1") (pinfunction "1_1") (pintype "passive"))
      (node (ref "C13") (pin "1") (pinfunction "1_1") (pintype "passive"))
      (node (ref "C14") (pin "1") (pinfunction "1_1") (pintype "passive"))
      (node (ref "U1") (pin "1H10") (pinfunction "VDD_LOGIC_4_1H10") (pintype "power_in"))
      (node (ref "U1") (pin "1H7") (pinfunction "VDD_LOGIC_1_1H7") (pintype "power_in"))
      (node (ref "U1") (pin "1H8") (pinfunction "VDD_LOGIC_2_1H8") (pintype "power_in"))
      (node (ref "U1") (pin "1H9") (pinfunction "VDD_LOGIC_3_1H9") (pintype "power_in"))
      (node (ref "U1") (pin "1J10") (pinfunction "VDD_LOGIC_6_1J10") (pintype "power_in"))
      (node (ref "U1") (pin "1J7") (pinfunction "VDD_LOGIC_5_1J7") (pintype "power_in"))
      (node (ref "U1") (pin "1K10") (pinfunction "VDD_LOGIC_8_1K10") (pintype "power_in"))
      (node (ref "U1") (pin "1K7") (pinfunction "VDD_LOGIC_7_1K7") (pintype "power_in"))
      (node (ref "U1") (pin "1L7") (pinfunction "VDD_LOGIC_9_1L7") (pintype "power_in"))
    )
    (net (code "10") (name "unconnected-(U1F-DDR_VREFOUT-Pad1H3)") (class "Default")
      (node (ref "U1") (pin "1H3") (pinfunction "DDR_VREFOUT_1H3") (pintype "output+no_connect"))
    )
    (net (code "11") (name "unconnected-(U1F-VCCIO5_1-Pad1N5)") (class "Default")
      (node (ref "U1") (pin "1N5") (pinfunction "VCCIO5_1_1N5") (pintype "power_in"))
    )
    (net (code "12") (name "unconnected-(U1F-VCCIO5_2-Pad1N6)") (class "Default")
      (node (ref "U1") (pin "1N6") (pinfunction "VCCIO5_2_1N6") (pintype "power_in"))
    )
    (net (code "13") (name "unconnected-(U1F-VCCIO6_1-Pad1L4)") (class "Default")
      (node (ref "U1") (pin "1L4") (pinfunction "VCCIO6_1_1L4") (pintype "power_in+no_connect"))
    )
    (net (code "14") (name "unconnected-(U1F-VCCIO6_2-Pad1L5)") (class "Default")
      (node (ref "U1") (pin "1L5") (pinfunction "VCCIO6_2_1L5") (pintype "power_in+no_connect"))
    )
    (net (code "15") (name "unconnected-(U1F-VCCIO7-Pad1N8)") (class "Default")
      (node (ref "U1") (pin "1N8") (pinfunction "VCCIO7_1N8") (pintype "power_in+no_connect"))
    )
  )
)
